# ProPrj_VL53L0X_1_2026-04-08.net
KiCad netlist of a schematic drawn in EasyEDA Pro
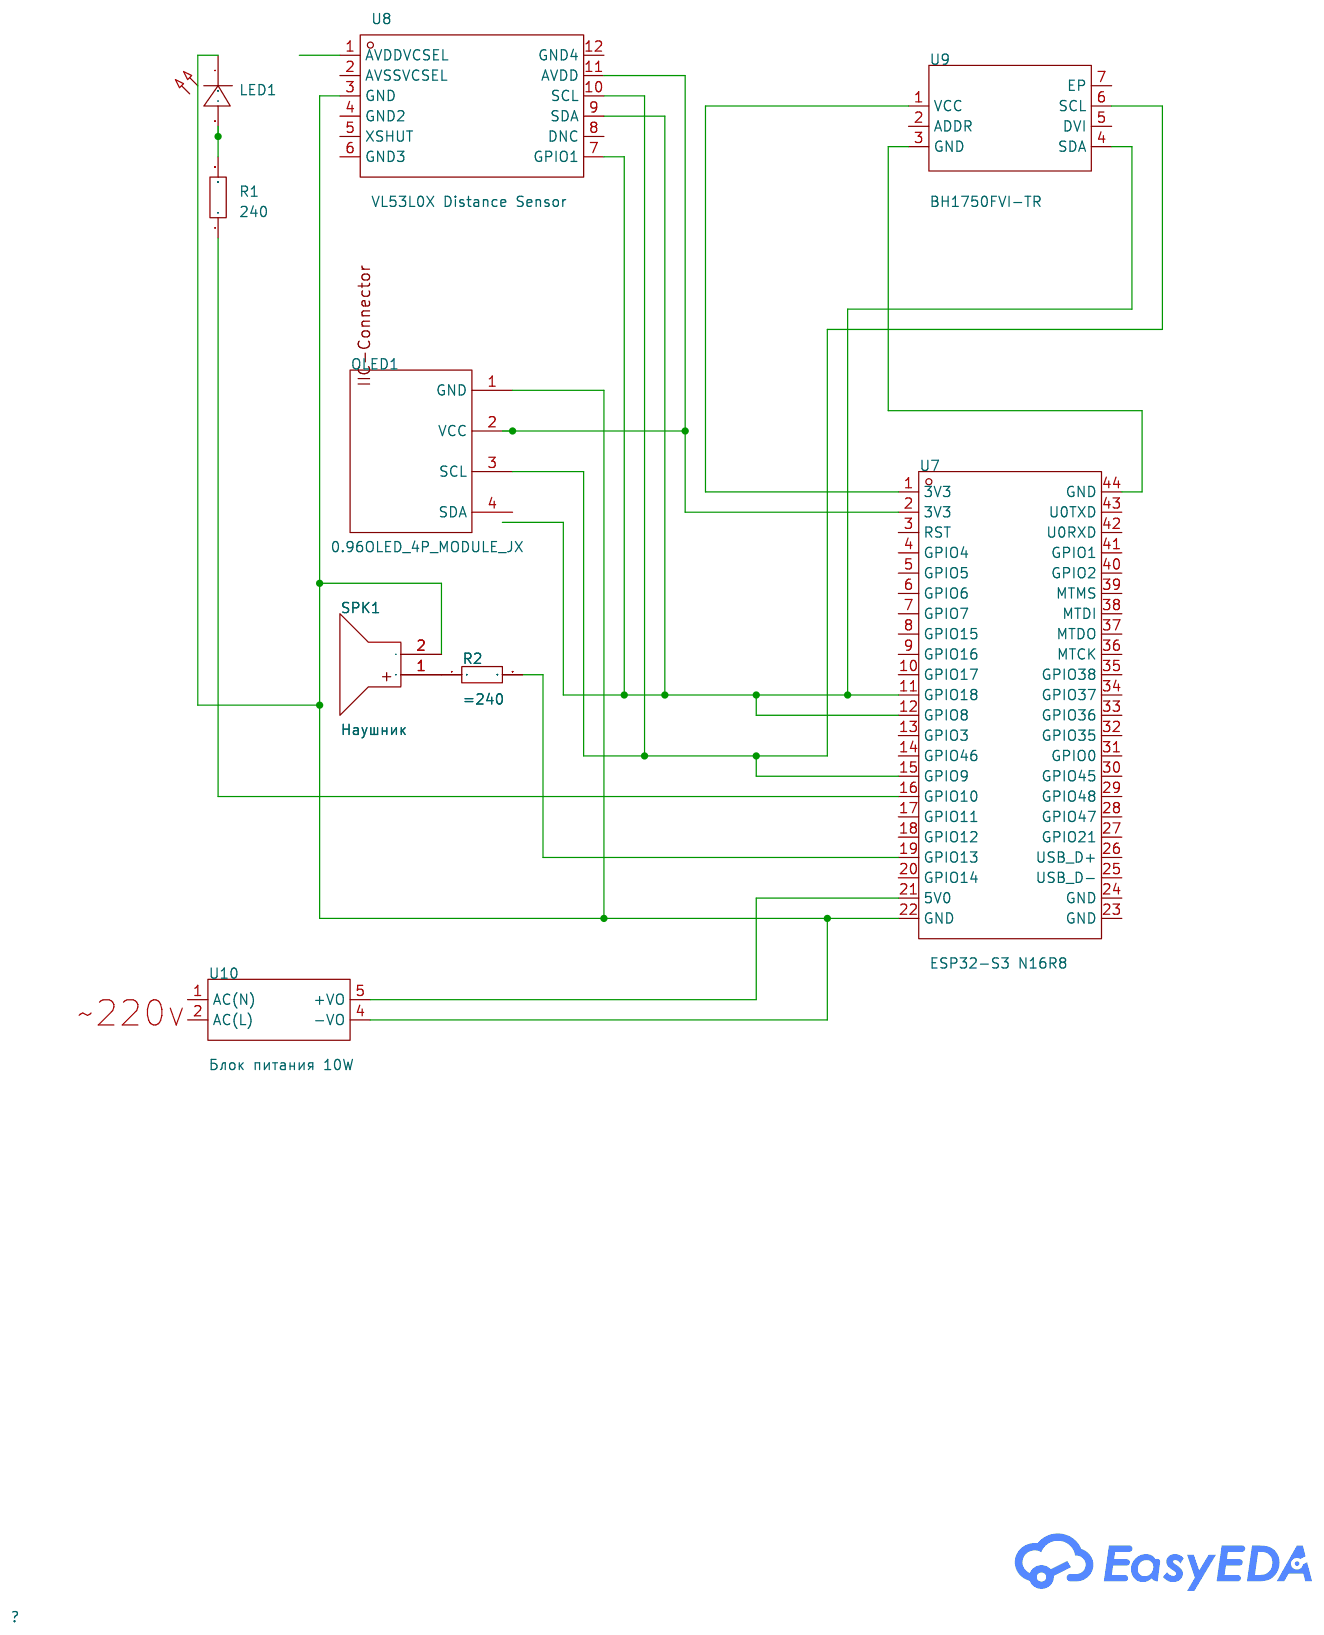
[diagram p0: schematic sheet]

(export (version "E")
  (design (tool "Eeschema 10.0.6"))
  (components
    (comp (ref "LED1")
      (value "~")
      (footprint "easyedapro:LED0603-RD_GREEN")
      (libsource (lib "easyedapro") (part "LED_G"))
    )
    (comp (ref "OLED1")
      (value "0.96OLED_4P_MODULE_JX")
      (footprint "easyedapro:0.96OLED_4P")
      (libsource (lib "easyedapro") (part "0.96OLED_4P_MODULE_JX"))
    )
    (comp (ref "R1") (value "10K") (footprint "easyedapro:R0603") (libsource (lib "easyedapro") (part "Res")))
    (comp (ref "R2") (value "10K") (footprint "easyedapro:R0603") (libsource (lib "easyedapro") (part "Res")))
    (comp (ref "SPK1")
      (value "Наушник")
      (footprint "easyedapro:SPK-TH_BD23.0-P10.00-D0.8-L-RD")
      (fields (field (name "Manufacturer Part") "2308 8Ω1w") (field (name "Manufacturer") "S&S(海旭)"))
      (libsource (lib "easyedapro") (part "2308 8Ω1W"))
    )
    (comp (ref "U7")
      (value "ESP32-S3 N16R8")
      (footprint "easyedapro:COMM-TH_L63.3-W25.4-P2.54-LS22.86")
      (fields (field (name "Manufacturer Part") "ESP32-S3-DEV-KIT-N8R8"))
      (libsource (lib "easyedapro") (part "ESP32-S3-DEV-KIT-N8R8"))
    )
    (comp (ref "U8")
      (value "VL53L0X Distance Sensor")
      (footprint "easyedapro:SENSOR-SMD_12P-L4.4-W2.4_VL53L0X")
      (fields (field (name "Manufacturer") "Waveshare(微雪电子)"))
      (libsource (lib "easyedapro") (part "VL53L0X DISTANCE SENSOR"))
    )
    (comp (ref "U9")
      (value "BH1750FVI-TR")
      (footprint "easyedapro:WSOF-6_L2.6-W1.6-P0.50-TL-EP")
      (fields (field (name "Manufacturer") "ROHM(罗姆)"))
      (libsource (lib "easyedapro") (part "BH1750FVI-TR"))
    )
    (comp (ref "U10")
      (value "Блок питания 10W")
      (footprint "easyedapro:PWRM-TH_LD05-23BXXR2")
      (fields (field (name "Manufacturer Part") "LD03-23B12R2") (field (name "Manufacturer") "YLPTEC(易川)"))
      (libsource (lib "easyedapro") (part "LD03-23B12R2_C46594383"))
    )
  )
  (nets
    (net (code "1") (name "Net-(LED1-A)") (class "Default")
      (node (ref "LED1") (pin "2") (pinfunction "A_2") (pintype "input"))
      (node (ref "R1") (pin "2") (pinfunction "2_2") (pintype "input"))
    )
    (net (code "2") (name "Net-(LED1-C)") (class "Default")
      (node (ref "LED1") (pin "1") (pinfunction "C_1") (pintype "input"))
      (node (ref "OLED1") (pin "1") (pinfunction "GND_1") (pintype "unspecified"))
      (node (ref "SPK1") (pin "2") (pinfunction "-_2") (pintype "unspecified"))
      (node (ref "U10") (pin "4") (pinfunction "-VO_4") (pintype "unspecified"))
      (node (ref "U7") (pin "22") (pinfunction "GND_22") (pintype "unspecified"))
      (node (ref "U8") (pin "3") (pinfunction "GND_3") (pintype "unspecified"))
    )
    (net (code "3") (name "Net-(OLED1-SCL)") (class "Default")
      (node (ref "OLED1") (pin "3") (pinfunction "SCL_3") (pintype "unspecified"))
      (node (ref "U7") (pin "15") (pinfunction "GPIO9_15") (pintype "unspecified"))
      (node (ref "U8") (pin "10") (pinfunction "SCL_10") (pintype "unspecified"))
      (node (ref "U9") (pin "6") (pinfunction "SCL_6") (pintype "unspecified"))
    )
    (net (code "4") (name "Net-(OLED1-VCC)") (class "Default")
      (node (ref "OLED1") (pin "2") (pinfunction "VCC_2") (pintype "unspecified"))
      (node (ref "U7") (pin "2") (pinfunction "3V3_2") (pintype "unspecified"))
      (node (ref "U8") (pin "11") (pinfunction "AVDD_11") (pintype "unspecified"))
    )
    (net (code "5") (name "Net-(SPK1-+)") (class "Default")
      (node (ref "R2") (pin "1") (pinfunction "1_1") (pintype "input"))
      (node (ref "SPK1") (pin "1") (pinfunction "+_1") (pintype "unspecified"))
    )
    (net (code "6") (name "Net-(U7-GPIO10)") (class "Default")
      (node (ref "R1") (pin "1") (pinfunction "1_1") (pintype "input"))
      (node (ref "U7") (pin "16") (pinfunction "GPIO10_16") (pintype "unspecified"))
    )
    (net (code "7") (name "Net-(U7-GPIO13)") (class "Default")
      (node (ref "R2") (pin "2") (pinfunction "2_2") (pintype "input"))
      (node (ref "U7") (pin "19") (pinfunction "GPIO13_19") (pintype "unspecified"))
    )
    (net (code "8") (name "Net-(U7-GPIO18)") (class "Default")
      (node (ref "U7") (pin "11") (pinfunction "GPIO18_11") (pintype "unspecified"))
      (node (ref "U7") (pin "12") (pinfunction "GPIO8_12") (pintype "unspecified"))
      (node (ref "U8") (pin "7") (pinfunction "GPIO1_7") (pintype "unspecified"))
      (node (ref "U8") (pin "9") (pinfunction "SDA_9") (pintype "unspecified"))
      (node (ref "U9") (pin "4") (pinfunction "SDA_4") (pintype "unspecified"))
    )
    (net (code "9") (name "Net-(U9-GND)") (class "Default")
      (node (ref "U7") (pin "44") (pinfunction "GND_44") (pintype "unspecified"))
      (node (ref "U9") (pin "3") (pinfunction "GND_3") (pintype "unspecified"))
    )
    (net (code "10") (name "Net-(U9-VCC)") (class "Default")
      (node (ref "U7") (pin "1") (pinfunction "3V3_1") (pintype "unspecified"))
      (node (ref "U9") (pin "1") (pinfunction "VCC_1") (pintype "unspecified"))
    )
    (net (code "11") (name "Net-(U10-+VO)") (class "Default")
      (node (ref "U10") (pin "5") (pinfunction "+VO_5") (pintype "unspecified"))
      (node (ref "U7") (pin "21") (pinfunction "5V0_21") (pintype "unspecified"))
    )
    (net (code "12") (name "unconnected-(OLED1-SDA-Pad4)") (class "Default")
      (node (ref "OLED1") (pin "4") (pinfunction "SDA_4") (pintype "unspecified"))
    )
    (net (code "13") (name "unconnected-(U7-GND-Pad23)") (class "Default")
      (node (ref "U7") (pin "23") (pinfunction "GND_23") (pintype "unspecified"))
    )
    (net (code "14") (name "unconnected-(U7-GND-Pad24)") (class "Default")
      (node (ref "U7") (pin "24") (pinfunction "GND_24") (pintype "unspecified"))
    )
    (net (code "15") (name "unconnected-(U7-GPIO0-Pad31)") (class "Default")
      (node (ref "U7") (pin "31") (pinfunction "GPIO0_31") (pintype "unspecified"))
    )
    (net (code "16") (name "unconnected-(U7-GPIO1-Pad41)") (class "Default")
      (node (ref "U7") (pin "41") (pinfunction "GPIO1_41") (pintype "unspecified"))
    )
    (net (code "17") (name "unconnected-(U7-GPIO2-Pad40)") (class "Default")
      (node (ref "U7") (pin "40") (pinfunction "GPIO2_40") (pintype "unspecified"))
    )
    (net (code "18") (name "unconnected-(U7-GPIO3-Pad13)") (class "Default")
      (node (ref "U7") (pin "13") (pinfunction "GPIO3_13") (pintype "unspecified"))
    )
    (net (code "19") (name "unconnected-(U7-GPIO4-Pad4)") (class "Default")
      (node (ref "U7") (pin "4") (pinfunction "GPIO4_4") (pintype "unspecified"))
    )
    (net (code "20") (name "unconnected-(U7-GPIO5-Pad5)") (class "Default")
      (node (ref "U7") (pin "5") (pinfunction "GPIO5_5") (pintype "unspecified"))
    )
    (net (code "21") (name "unconnected-(U7-GPIO6-Pad6)") (class "Default")
      (node (ref "U7") (pin "6") (pinfunction "GPIO6_6") (pintype "unspecified"))
    )
    (net (code "22") (name "unconnected-(U7-GPIO7-Pad7)") (class "Default")
      (node (ref "U7") (pin "7") (pinfunction "GPIO7_7") (pintype "unspecified"))
    )
    (net (code "23") (name "unconnected-(U7-GPIO11-Pad17)") (class "Default")
      (node (ref "U7") (pin "17") (pinfunction "GPIO11_17") (pintype "unspecified"))
    )
    (net (code "24") (name "unconnected-(U7-GPIO12-Pad18)") (class "Default")
      (node (ref "U7") (pin "18") (pinfunction "GPIO12_18") (pintype "unspecified"))
    )
    (net (code "25") (name "unconnected-(U7-GPIO14-Pad20)") (class "Default")
      (node (ref "U7") (pin "20") (pinfunction "GPIO14_20") (pintype "unspecified"))
    )
    (net (code "26") (name "unconnected-(U7-GPIO15-Pad8)") (class "Default")
      (node (ref "U7") (pin "8") (pinfunction "GPIO15_8") (pintype "unspecified"))
    )
    (net (code "27") (name "unconnected-(U7-GPIO16-Pad9)") (class "Default")
      (node (ref "U7") (pin "9") (pinfunction "GPIO16_9") (pintype "unspecified"))
    )
    (net (code "28") (name "unconnected-(U7-GPIO17-Pad10)") (class "Default")
      (node (ref "U7") (pin "10") (pinfunction "GPIO17_10") (pintype "unspecified"))
    )
    (net (code "29") (name "unconnected-(U7-GPIO21-Pad27)") (class "Default")
      (node (ref "U7") (pin "27") (pinfunction "GPIO21_27") (pintype "unspecified"))
    )
    (net (code "30") (name "unconnected-(U7-GPIO35-Pad32)") (class "Default")
      (node (ref "U7") (pin "32") (pinfunction "GPIO35_32") (pintype "unspecified"))
    )
    (net (code "31") (name "unconnected-(U7-GPIO36-Pad33)") (class "Default")
      (node (ref "U7") (pin "33") (pinfunction "GPIO36_33") (pintype "unspecified"))
    )
    (net (code "32") (name "unconnected-(U7-GPIO37-Pad34)") (class "Default")
      (node (ref "U7") (pin "34") (pinfunction "GPIO37_34") (pintype "unspecified"))
    )
    (net (code "33") (name "unconnected-(U7-GPIO38-Pad35)") (class "Default")
      (node (ref "U7") (pin "35") (pinfunction "GPIO38_35") (pintype "unspecified"))
    )
    (net (code "34") (name "unconnected-(U7-GPIO45-Pad30)") (class "Default")
      (node (ref "U7") (pin "30") (pinfunction "GPIO45_30") (pintype "unspecified"))
    )
    (net (code "35") (name "unconnected-(U7-GPIO46-Pad14)") (class "Default")
      (node (ref "U7") (pin "14") (pinfunction "GPIO46_14") (pintype "unspecified"))
    )
    (net (code "36") (name "unconnected-(U7-GPIO47-Pad28)") (class "Default")
      (node (ref "U7") (pin "28") (pinfunction "GPIO47_28") (pintype "unspecified"))
    )
    (net (code "37") (name "unconnected-(U7-GPIO48-Pad29)") (class "Default")
      (node (ref "U7") (pin "29") (pinfunction "GPIO48_29") (pintype "unspecified"))
    )
    (net (code "38") (name "unconnected-(U7-MTCK-Pad36)") (class "Default")
      (node (ref "U7") (pin "36") (pinfunction "MTCK_36") (pintype "unspecified"))
    )
    (net (code "39") (name "unconnected-(U7-MTDI-Pad38)") (class "Default")
      (node (ref "U7") (pin "38") (pinfunction "MTDI_38") (pintype "unspecified"))
    )
    (net (code "40") (name "unconnected-(U7-MTDO-Pad37)") (class "Default")
      (node (ref "U7") (pin "37") (pinfunction "MTDO_37") (pintype "unspecified"))
    )
    (net (code "41") (name "unconnected-(U7-MTMS-Pad39)") (class "Default")
      (node (ref "U7") (pin "39") (pinfunction "MTMS_39") (pintype "unspecified"))
    )
    (net (code "42") (name "unconnected-(U7-RST-Pad3)") (class "Default")
      (node (ref "U7") (pin "3") (pinfunction "RST_3") (pintype "unspecified"))
    )
    (net (code "43") (name "unconnected-(U7-U0RXD-Pad42)") (class "Default")
      (node (ref "U7") (pin "42") (pinfunction "U0RXD_42") (pintype "unspecified"))
    )
    (net (code "44") (name "unconnected-(U7-U0TXD-Pad43)") (class "Default")
      (node (ref "U7") (pin "43") (pinfunction "U0TXD_43") (pintype "unspecified"))
    )
    (net (code "45") (name "unconnected-(U7-USB_D+-Pad26)") (class "Default")
      (node (ref "U7") (pin "26") (pinfunction "USB_D+_26") (pintype "unspecified"))
    )
    (net (code "46") (name "unconnected-(U7-USB_D--Pad25)") (class "Default")
      (node (ref "U7") (pin "25") (pinfunction "USB_D-_25") (pintype "unspecified"))
    )
    (net (code "47") (name "unconnected-(U8-AVDDVCSEL-Pad1)") (class "Default")
      (node (ref "U8") (pin "1") (pinfunction "AVDDVCSEL_1") (pintype "unspecified"))
    )
    (net (code "48") (name "unconnected-(U8-AVSSVCSEL-Pad2)") (class "Default")
      (node (ref "U8") (pin "2") (pinfunction "AVSSVCSEL_2") (pintype "unspecified"))
    )
    (net (code "49") (name "unconnected-(U8-DNC-Pad8)") (class "Default")
      (node (ref "U8") (pin "8") (pinfunction "DNC_8") (pintype "unspecified"))
    )
    (net (code "50") (name "unconnected-(U8-GND2-Pad4)") (class "Default")
      (node (ref "U8") (pin "4") (pinfunction "GND2_4") (pintype "unspecified"))
    )
    (net (code "51") (name "unconnected-(U8-GND3-Pad6)") (class "Default")
      (node (ref "U8") (pin "6") (pinfunction "GND3_6") (pintype "unspecified"))
    )
    (net (code "52") (name "unconnected-(U8-GND4-Pad12)") (class "Default")
      (node (ref "U8") (pin "12") (pinfunction "GND4_12") (pintype "unspecified"))
    )
    (net (code "53") (name "unconnected-(U8-XSHUT-Pad5)") (class "Default")
      (node (ref "U8") (pin "5") (pinfunction "XSHUT_5") (pintype "unspecified"))
    )
    (net (code "54") (name "unconnected-(U9-ADDR-Pad2)") (class "Default")
      (node (ref "U9") (pin "2") (pinfunction "ADDR_2") (pintype "unspecified"))
    )
    (net (code "55") (name "unconnected-(U9-DVI-Pad5)") (class "Default")
      (node (ref "U9") (pin "5") (pinfunction "DVI_5") (pintype "unspecified"))
    )
    (net (code "56") (name "unconnected-(U9-EP-Pad7)") (class "Default")
      (node (ref "U9") (pin "7") (pinfunction "EP_7") (pintype "unspecified"))
    )
    (net (code "57") (name "unconnected-(U10-AC(L)-Pad2)") (class "Default")
      (node (ref "U10") (pin "2") (pinfunction "AC(L)_2") (pintype "unspecified"))
    )
    (net (code "58") (name "unconnected-(U10-AC(N)-Pad1)") (class "Default")
      (node (ref "U10") (pin "1") (pinfunction "AC(N)_1") (pintype "unspecified"))
    )
  )
)
